# Offboard_Kinen_Expansion.net
KiCad netlist of a schematic drawn in Altium Designer
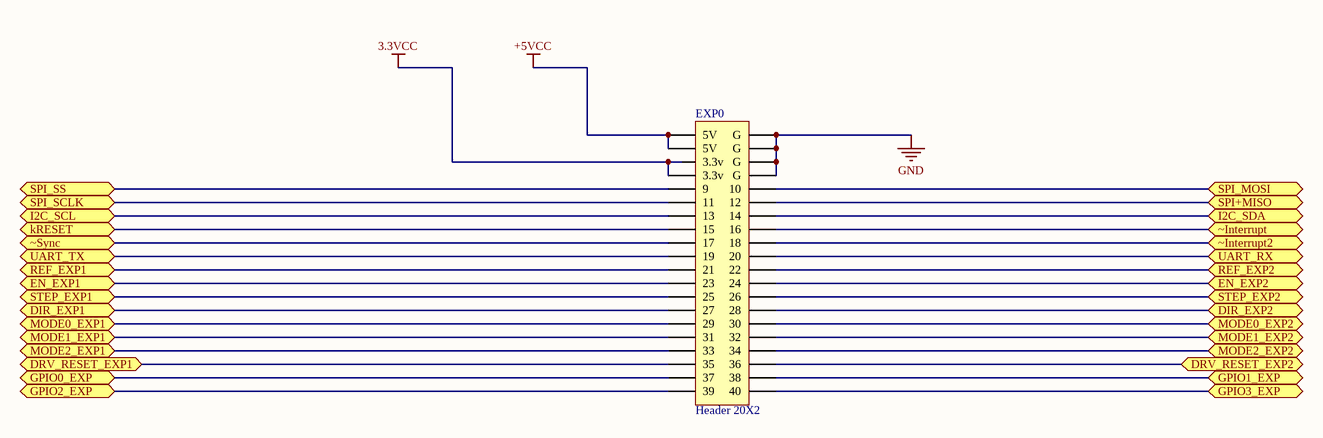
[diagram p0: Offboard Kinen Expansion.SchDoc]

(export (version "E")
  (design (tool "Eeschema 10.0.6"))
  (components
    (comp (ref "EXP0")
      (value "Header 20X2")
      (footprint "HDR2X20")
      (description "Header, 20-Pin, Dual row")
      (fields (field (name "PUBLISHER") "Altium Limited"))
      (libsource (lib "Miscellaneous Connectors") (part "Header 20X2"))
    )
  )
  (nets
    (net (code "1") (name "+5VCC") (class "Default")
      (node (ref "EXP0") (pin "1") (pinfunction "5V_1") (pintype "passive"))
      (node (ref "EXP0") (pin "3") (pinfunction "5V_3") (pintype "passive"))
    )
    (net (code "2") (name "/DIR_EXP1") (class "Default")
      (node (ref "EXP0") (pin "27") (pinfunction "27_27") (pintype "passive"))
    )
    (net (code "3") (name "/DIR_EXP2") (class "Default")
      (node (ref "EXP0") (pin "28") (pinfunction "28_28") (pintype "passive"))
    )
    (net (code "4") (name "/DRV_RESET_EXP1") (class "Default")
      (node (ref "EXP0") (pin "35") (pinfunction "35_35") (pintype "passive"))
    )
    (net (code "5") (name "/DRV_RESET_EXP2") (class "Default")
      (node (ref "EXP0") (pin "36") (pinfunction "36_36") (pintype "passive"))
    )
    (net (code "6") (name "/EN_EXP1") (class "Default")
      (node (ref "EXP0") (pin "23") (pinfunction "23_23") (pintype "passive"))
    )
    (net (code "7") (name "/EN_EXP2") (class "Default")
      (node (ref "EXP0") (pin "24") (pinfunction "24_24") (pintype "passive"))
    )
    (net (code "8") (name "/GPIO0_EXP") (class "Default")
      (node (ref "EXP0") (pin "37") (pinfunction "37_37") (pintype "passive"))
    )
    (net (code "9") (name "/GPIO1_EXP") (class "Default")
      (node (ref "EXP0") (pin "38") (pinfunction "38_38") (pintype "passive"))
    )
    (net (code "10") (name "/GPIO2_EXP") (class "Default")
      (node (ref "EXP0") (pin "39") (pinfunction "39_39") (pintype "passive"))
    )
    (net (code "11") (name "/GPIO3_EXP") (class "Default")
      (node (ref "EXP0") (pin "40") (pinfunction "40_40") (pintype "passive"))
    )
    (net (code "12") (name "/I2C_SCL") (class "Default")
      (node (ref "EXP0") (pin "13") (pinfunction "13_13") (pintype "passive"))
    )
    (net (code "13") (name "/I2C_SDA") (class "Default")
      (node (ref "EXP0") (pin "14") (pinfunction "14_14") (pintype "passive"))
    )
    (net (code "14") (name "/MODE0_EXP1") (class "Default")
      (node (ref "EXP0") (pin "29") (pinfunction "29_29") (pintype "passive"))
    )
    (net (code "15") (name "/MODE0_EXP2") (class "Default")
      (node (ref "EXP0") (pin "30") (pinfunction "30_30") (pintype "passive"))
    )
    (net (code "16") (name "/MODE1_EXP1") (class "Default")
      (node (ref "EXP0") (pin "31") (pinfunction "31_31") (pintype "passive"))
    )
    (net (code "17") (name "/MODE1_EXP2") (class "Default")
      (node (ref "EXP0") (pin "32") (pinfunction "32_32") (pintype "passive"))
    )
    (net (code "18") (name "/MODE2_EXP1") (class "Default")
      (node (ref "EXP0") (pin "33") (pinfunction "33_33") (pintype "passive"))
    )
    (net (code "19") (name "/MODE2_EXP2") (class "Default")
      (node (ref "EXP0") (pin "34") (pinfunction "34_34") (pintype "passive"))
    )
    (net (code "20") (name "/REF_EXP1") (class "Default")
      (node (ref "EXP0") (pin "21") (pinfunction "21_21") (pintype "passive"))
    )
    (net (code "21") (name "/REF_EXP2") (class "Default")
      (node (ref "EXP0") (pin "22") (pinfunction "22_22") (pintype "passive"))
    )
    (net (code "22") (name "/SPI+MISO") (class "Default")
      (node (ref "EXP0") (pin "12") (pinfunction "12_12") (pintype "passive"))
    )
    (net (code "23") (name "/SPI_MOSI") (class "Default")
      (node (ref "EXP0") (pin "10") (pinfunction "10_10") (pintype "passive"))
    )
    (net (code "24") (name "/SPI_SCLK") (class "Default")
      (node (ref "EXP0") (pin "11") (pinfunction "11_11") (pintype "passive"))
    )
    (net (code "25") (name "/SPI_SS") (class "Default")
      (node (ref "EXP0") (pin "9") (pinfunction "9_9") (pintype "passive"))
    )
    (net (code "26") (name "/STEP_EXP1") (class "Default")
      (node (ref "EXP0") (pin "25") (pinfunction "25_25") (pintype "passive"))
    )
    (net (code "27") (name "/STEP_EXP2") (class "Default")
      (node (ref "EXP0") (pin "26") (pinfunction "26_26") (pintype "passive"))
    )
    (net (code "28") (name "/UART_RX") (class "Default")
      (node (ref "EXP0") (pin "20") (pinfunction "20_20") (pintype "passive"))
    )
    (net (code "29") (name "/UART_TX") (class "Default")
      (node (ref "EXP0") (pin "19") (pinfunction "19_19") (pintype "passive"))
    )
    (net (code "30") (name "/kRESET") (class "Default")
      (node (ref "EXP0") (pin "15") (pinfunction "15_15") (pintype "passive"))
    )
    (net (code "31") (name "/~Interrupt") (class "Default")
      (node (ref "EXP0") (pin "16") (pinfunction "16_16") (pintype "passive"))
    )
    (net (code "32") (name "/~Interrupt2") (class "Default")
      (node (ref "EXP0") (pin "18") (pinfunction "18_18") (pintype "passive"))
    )
    (net (code "33") (name "/~Sync") (class "Default")
      (node (ref "EXP0") (pin "17") (pinfunction "17_17") (pintype "passive"))
    )
    (net (code "34") (name "3.3VCC") (class "Default")
      (node (ref "EXP0") (pin "5") (pinfunction "3.3v_5") (pintype "passive"))
      (node (ref "EXP0") (pin "7") (pinfunction "3.3v_7") (pintype "passive"))
    )
    (net (code "35") (name "GND") (class "Default")
      (node (ref "EXP0") (pin "2") (pinfunction "G_2") (pintype "passive"))
      (node (ref "EXP0") (pin "4") (pinfunction "G_4") (pintype "passive"))
      (node (ref "EXP0") (pin "6") (pinfunction "G_6") (pintype "passive"))
      (node (ref "EXP0") (pin "8") (pinfunction "G_8") (pintype "passive"))
    )
  )
)
